# Combined_Board_BMI088.net
KiCad netlist of a schematic drawn in EAGLE
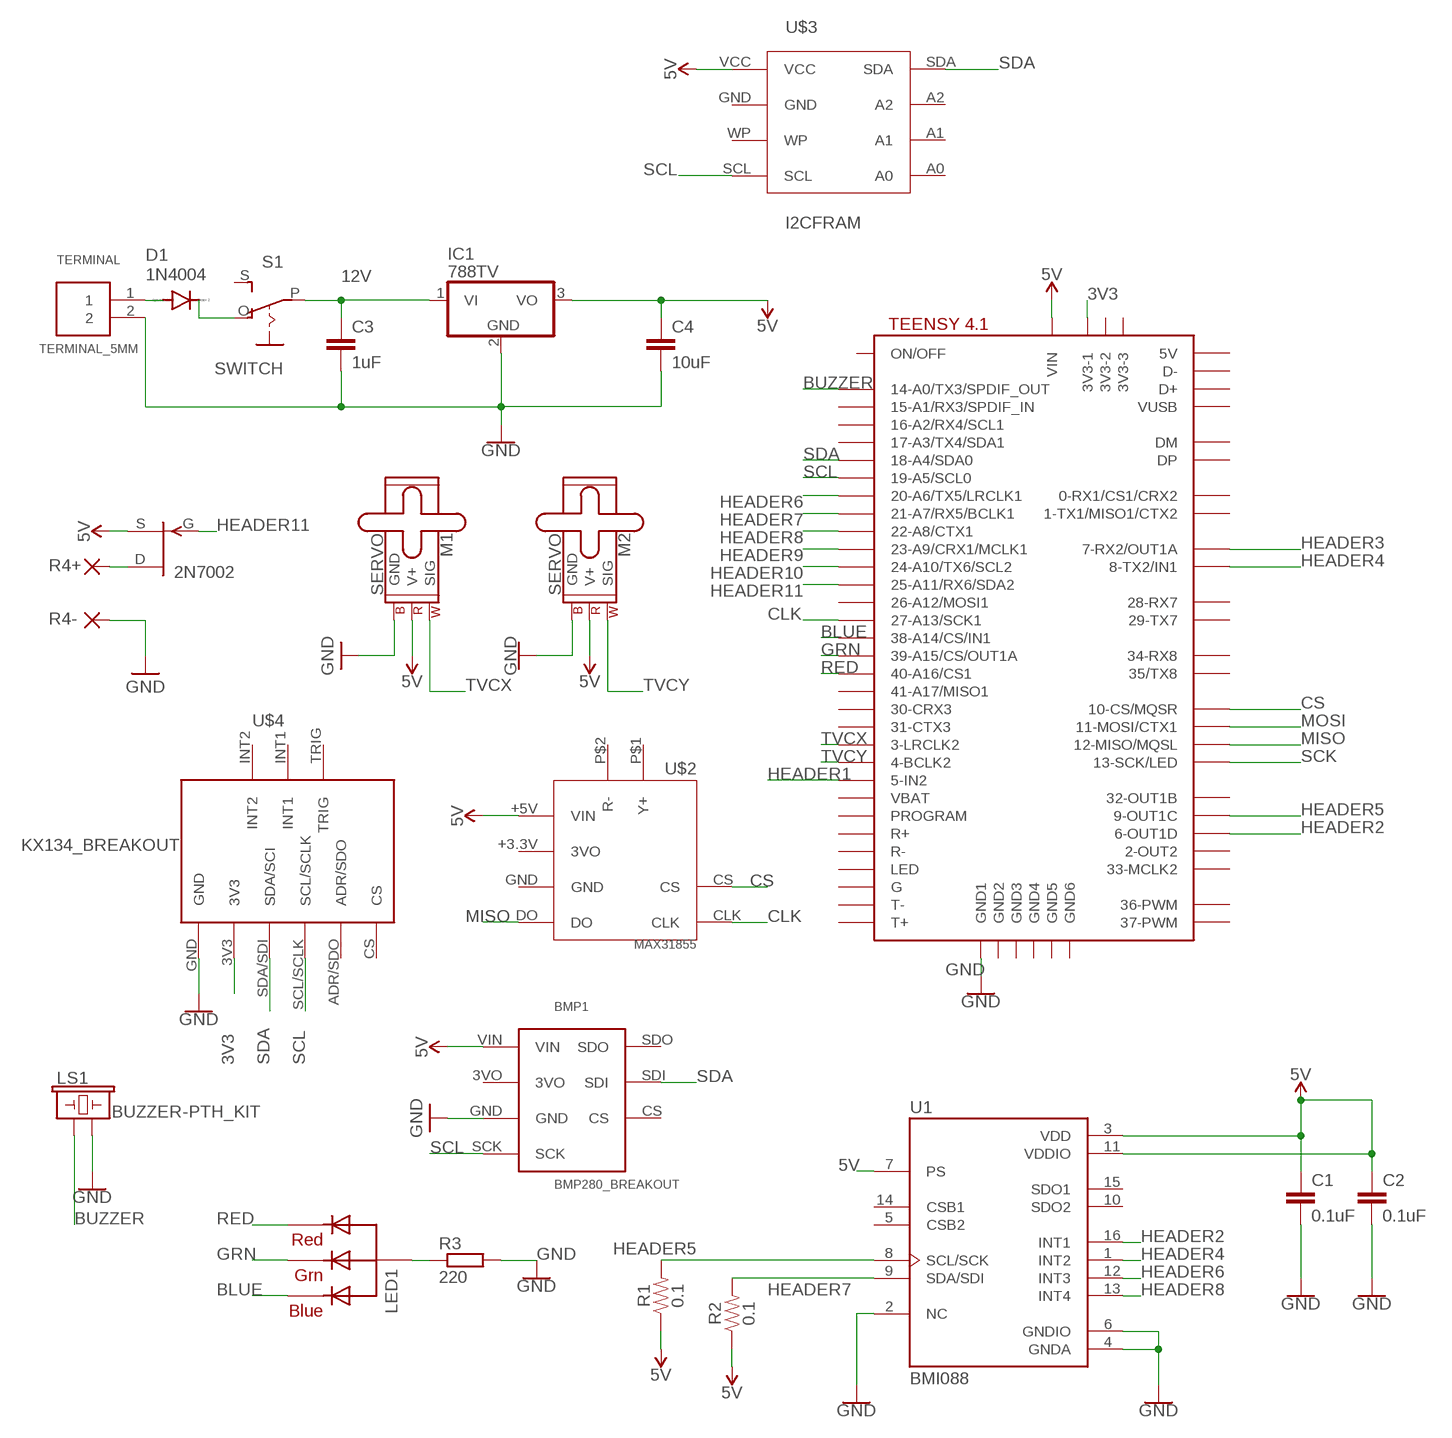
[diagram p0: schematic, sheet 1]

(export (version "E")
  (design (tool "Eeschema 10.0.6"))
  (components
    (comp (ref "2N7002")
      (value "2N3819")
      (footprint "eagle-import:TO92")
      (libsource (lib "eagle-import") (part "2N3819"))
    )
    (comp (ref "BMP1")
      (value "BMP280_BREAKOUT")
      (footprint "eagle-import:BMP280_BREAKOUT")
      (libsource (lib "eagle-import") (part "BMP280_BREAKOUT"))
    )
    (comp (ref "C1")
      (value "0.1uF")
      (footprint "eagle-import:0402")
      (libsource (lib "eagle-import") (part "0.1UF-0402-16V-10%"))
    )
    (comp (ref "C2")
      (value "0.1uF")
      (footprint "eagle-import:0402")
      (libsource (lib "eagle-import") (part "0.1UF-0402-16V-10%"))
    )
    (comp (ref "C3")
      (value "1uF")
      (footprint "eagle-import:CAP-PTH-2.54")
      (libsource (lib "eagle-import") (part "22PF-PTH-2.54MM-200V-5%"))
    )
    (comp (ref "C4")
      (value "10uF")
      (footprint "eagle-import:CAP-PTH-2.54")
      (libsource (lib "eagle-import") (part "22PF-PTH-2.54MM-200V-5%"))
    )
    (comp (ref "D1")
      (value "1N4004")
      (footprint "eagle-import:DO41-10")
      (libsource (lib "eagle-import") (part "1N4004"))
    )
    (comp (ref "IC1")
      (value "788TV")
      (footprint "eagle-import:TO220V")
      (libsource (lib "eagle-import") (part "78TV8"))
    )
    (comp (ref "LED1")
      (value "RGBLED_CA-5MM")
      (footprint "eagle-import:LED5MMRGB")
      (libsource (lib "eagle-import") (part "RGBLED_CA-5MM"))
    )
    (comp (ref "LS1")
      (value "BUZZER-PTH_KIT")
      (footprint "eagle-import:BUZZER-12MM-KIT")
      (libsource (lib "eagle-import") (part "BUZZER-PTH_KIT"))
    )
    (comp (ref "M1")
      (value "SERVO")
      (footprint "eagle-import:1X03")
      (libsource (lib "eagle-import") (part "SERVO"))
    )
    (comp (ref "M2")
      (value "SERVO")
      (footprint "eagle-import:1X03")
      (libsource (lib "eagle-import") (part "SERVO"))
    )
    (comp (ref "R1")
      (value "0.1")
      (footprint "eagle-import:0603")
      (libsource (lib "eagle-import") (part "0.1OHM-0603-1/3W-1%"))
    )
    (comp (ref "R2")
      (value "0.1")
      (footprint "eagle-import:0603")
      (libsource (lib "eagle-import") (part "0.1OHM-0603-1/3W-1%"))
    )
    (comp (ref "R3")
      (value "220")
      (footprint "eagle-import:0204_7")
      (libsource (lib "eagle-import") (part "R-EU_0204/7"))
    )
    (comp (ref "R4+")
      (value "1,6/0,8")
      (footprint "eagle-import:1,6_0,8")
      (libsource (lib "eagle-import") (part "1,6/0,8"))
    )
    (comp (ref "R4-")
      (value "1,6/0,8")
      (footprint "eagle-import:1,6_0,8")
      (libsource (lib "eagle-import") (part "1,6/0,8"))
    )
    (comp (ref "S1")
      (value "SWITCH")
      (footprint "eagle-import:EG1218")
      (libsource (lib "eagle-import") (part "EG1218S"))
    )
    (comp (ref "TERMINAL")
      (value "TERMINAL_5MM")
      (footprint "eagle-import:TERMINAL_5MM")
      (libsource (lib "eagle-import") (part "TERMINAL_5MM"))
    )
    (comp (ref "U$1")
      (value "TEENSY41")
      (footprint "eagle-import:TEENSY41")
      (libsource (lib "eagle-import") (part "TEENSY41"))
    )
    (comp (ref "U$2")
      (value "MAX31855")
      (footprint "eagle-import:MAX31855-BREAKOUT")
      (libsource (lib "eagle-import") (part "MAX31855"))
    )
    (comp (ref "U$3")
      (value "I2CFRAM")
      (footprint "eagle-import:I2CFRAM")
      (libsource (lib "eagle-import") (part "I2CFRAM"))
    )
    (comp (ref "U$4")
      (value "KX134_BREAKOUT")
      (footprint "eagle-import:KX134_BREAKOUT")
      (libsource (lib "eagle-import") (part "KX134_BREAKOUT"))
    )
    (comp (ref "U1")
      (value "BMI088")
      (footprint "eagle-import:PQFN50P450X300X100-16N")
      (fields (field (name "MF") "Bosch Sensortec"))
      (libsource (lib "eagle-import") (part "BMI088"))
    )
  )
  (nets
    (net (code "1") (name "/3V3") (class "Default")
      (node (ref "U$1") (pin "3V3-1") (pinfunction "3V3-1_3V3-1") (pintype "bidirectional"))
      (node (ref "U$4") (pin "3V3") (pinfunction "3V3_3V3") (pintype "bidirectional"))
    )
    (net (code "2") (name "/12V") (class "Default")
      (node (ref "C3") (pin "1") (pinfunction "1_1") (pintype "passive"))
      (node (ref "IC1") (pin "1") (pinfunction "VI_1") (pintype "input"))
      (node (ref "S1") (pin "P") (pinfunction "P_P") (pintype "passive"))
    )
    (net (code "3") (name "/BLUE") (class "Default")
      (node (ref "LED1") (pin "4") (pinfunction "BLUE_4") (pintype "bidirectional"))
      (node (ref "U$1") (pin "38-A14/CS/IN1") (pinfunction "38-A14/CS/IN1_38-A14/CS/IN1") (pintype "bidirectional"))
    )
    (net (code "4") (name "/BUZZER") (class "Default")
      (node (ref "LS1") (pin "+") (pinfunction "1_+") (pintype "passive"))
      (node (ref "U$1") (pin "14-A0/TX3/SPDIF_OUT") (pinfunction "14-A0/TX3/SPDIF_OUT_14-A0/TX3/SPDIF_OUT") (pintype "bidirectional"))
    )
    (net (code "5") (name "/CLK") (class "Default")
      (node (ref "U$1") (pin "27-A13/SCK1") (pinfunction "27-A13/SCK1_27-A13/SCK1") (pintype "bidirectional"))
      (node (ref "U$2") (pin "CLK") (pinfunction "CLK_CLK") (pintype "input"))
    )
    (net (code "6") (name "/CS") (class "Default")
      (node (ref "U$1") (pin "10-CS\\MQSR") (pinfunction "10-CS/MQSR_10-CS\\MQSR") (pintype "bidirectional"))
      (node (ref "U$2") (pin "CS") (pinfunction "CS_CS") (pintype "input"))
    )
    (net (code "7") (name "/GRN") (class "Default")
      (node (ref "LED1") (pin "3") (pinfunction "GREEN_3") (pintype "bidirectional"))
      (node (ref "U$1") (pin "39-A15/CS/OUT1A") (pinfunction "39-A15/CS/OUT1A_39-A15/CS/OUT1A") (pintype "bidirectional"))
    )
    (net (code "8") (name "/HEADER1") (class "Default")
      (node (ref "U$1") (pin "5-IN2") (pinfunction "5-IN2_5-IN2") (pintype "bidirectional"))
    )
    (net (code "9") (name "/HEADER2") (class "Default")
      (node (ref "U$1") (pin "6-OUT1D") (pinfunction "6-OUT1D_6-OUT1D") (pintype "bidirectional"))
      (node (ref "U1") (pin "16") (pinfunction "INT1_16") (pintype "bidirectional"))
    )
    (net (code "10") (name "/HEADER3") (class "Default")
      (node (ref "U$1") (pin "7-RX2/OUT1A") (pinfunction "7-RX2/OUT1A_7-RX2/OUT1A") (pintype "bidirectional"))
    )
    (net (code "11") (name "/HEADER4") (class "Default")
      (node (ref "U$1") (pin "8-TX2/IN2") (pinfunction "8-TX2/IN1_8-TX2/IN2") (pintype "bidirectional"))
      (node (ref "U1") (pin "1") (pinfunction "INT2_1") (pintype "bidirectional"))
    )
    (net (code "12") (name "/HEADER5") (class "Default")
      (node (ref "R1") (pin "2") (pinfunction "2_2") (pintype "passive"))
      (node (ref "U$1") (pin "9-OUT1C") (pinfunction "9-OUT1C_9-OUT1C") (pintype "bidirectional"))
      (node (ref "U1") (pin "8") (pinfunction "SCL/SCK_8") (pintype "input"))
    )
    (net (code "13") (name "/HEADER6") (class "Default")
      (node (ref "U$1") (pin "20-A6/TX5/LRCLK1") (pinfunction "20-A6/TX5/LRCLK1_20-A6/TX5/LRCLK1") (pintype "bidirectional"))
      (node (ref "U1") (pin "12") (pinfunction "INT3_12") (pintype "bidirectional"))
    )
    (net (code "14") (name "/HEADER7") (class "Default")
      (node (ref "R2") (pin "2") (pinfunction "2_2") (pintype "passive"))
      (node (ref "U$1") (pin "21-A7/RX5/BCLK1") (pinfunction "21-A7/RX5/BCLK1_21-A7/RX5/BCLK1") (pintype "bidirectional"))
      (node (ref "U1") (pin "9") (pinfunction "SDA/SDI_9") (pintype "bidirectional"))
    )
    (net (code "15") (name "/HEADER8") (class "Default")
      (node (ref "U$1") (pin "22-A8/CTX1") (pinfunction "22-A8/CTX1_22-A8/CTX1") (pintype "bidirectional"))
      (node (ref "U1") (pin "13") (pinfunction "INT4_13") (pintype "bidirectional"))
    )
    (net (code "16") (name "/HEADER9") (class "Default")
      (node (ref "U$1") (pin "23-A9/CRX1/MCLK1") (pinfunction "23-A9/CRX1/MCLK1_23-A9/CRX1/MCLK1") (pintype "bidirectional"))
    )
    (net (code "17") (name "/HEADER10") (class "Default")
      (node (ref "U$1") (pin "24-A10/TX6/SCL2") (pinfunction "24-A10/TX6/SCL2_24-A10/TX6/SCL2") (pintype "bidirectional"))
    )
    (net (code "18") (name "/HEADER11") (class "Default")
      (node (ref "2N7002") (pin "2") (pinfunction "G_2") (pintype "passive"))
      (node (ref "U$1") (pin "25-A11/RX6/SDA2") (pinfunction "25-A11/RX6/SDA2_25-A11/RX6/SDA2") (pintype "bidirectional"))
    )
    (net (code "19") (name "/MISO") (class "Default")
      (node (ref "U$1") (pin "12-MISO/MQSL") (pinfunction "12-MISO/MQSL_12-MISO/MQSL") (pintype "bidirectional"))
      (node (ref "U$2") (pin "DO") (pinfunction "DO_DO") (pintype "output"))
    )
    (net (code "20") (name "/MOSI") (class "Default")
      (node (ref "U$1") (pin "11-MOSI/CTX1") (pinfunction "11-MOSI/CTX1_11-MOSI/CTX1") (pintype "bidirectional"))
    )
    (net (code "21") (name "/RED") (class "Default")
      (node (ref "LED1") (pin "1") (pinfunction "RED_1") (pintype "bidirectional"))
      (node (ref "U$1") (pin "40-A16/CS1") (pinfunction "40-A16/CS1_40-A16/CS1") (pintype "bidirectional"))
    )
    (net (code "22") (name "/SCK") (class "Default")
      (node (ref "U$1") (pin "13-SCK/LED") (pinfunction "13-SCK/LED_13-SCK/LED") (pintype "bidirectional"))
    )
    (net (code "23") (name "/SCL") (class "Default")
      (node (ref "BMP1") (pin "SCK") (pinfunction "SCK_SCK") (pintype "bidirectional"))
      (node (ref "U$1") (pin "19-A5/SCL0") (pinfunction "19-A5/SCL0_19-A5/SCL0") (pintype "bidirectional"))
      (node (ref "U$3") (pin "SCL") (pinfunction "SCL_SCL") (pintype "bidirectional"))
      (node (ref "U$4") (pin "SCL/SCLK") (pinfunction "SCL/SCLK_SCL/SCLK") (pintype "bidirectional"))
    )
    (net (code "24") (name "/SDA") (class "Default")
      (node (ref "BMP1") (pin "SDI") (pinfunction "SDI_SDI") (pintype "bidirectional"))
      (node (ref "U$1") (pin "18-A4/SDA0") (pinfunction "18-A4/SDA0_18-A4/SDA0") (pintype "bidirectional"))
      (node (ref "U$3") (pin "SDA") (pinfunction "SDA_SDA") (pintype "bidirectional"))
      (node (ref "U$4") (pin "SDA/SDI") (pinfunction "SDA/SCI_SDA/SDI") (pintype "bidirectional"))
    )
    (net (code "25") (name "/TVCX") (class "Default")
      (node (ref "M1") (pin "1") (pinfunction "SIG_1") (pintype "bidirectional"))
      (node (ref "U$1") (pin "3-LRCLK2") (pinfunction "3-LRCLK2_3-LRCLK2") (pintype "bidirectional"))
    )
    (net (code "26") (name "/TVCY") (class "Default")
      (node (ref "M2") (pin "1") (pinfunction "SIG_1") (pintype "bidirectional"))
      (node (ref "U$1") (pin "4-BCLK2") (pinfunction "4-BCLK2_4-BCLK2") (pintype "bidirectional"))
    )
    (net (code "27") (name "5V") (class "Default")
      (node (ref "2N7002") (pin "3") (pinfunction "S_3") (pintype "passive"))
      (node (ref "BMP1") (pin "VIN") (pinfunction "VIN_VIN") (pintype "bidirectional"))
      (node (ref "C1") (pin "1") (pinfunction "1_1") (pintype "passive"))
      (node (ref "C2") (pin "1") (pinfunction "1_1") (pintype "passive"))
      (node (ref "C4") (pin "1") (pinfunction "1_1") (pintype "passive"))
      (node (ref "IC1") (pin "3") (pinfunction "VO_3") (pintype "passive"))
      (node (ref "M1") (pin "2") (pinfunction "V+_2") (pintype "bidirectional"))
      (node (ref "M2") (pin "2") (pinfunction "V+_2") (pintype "bidirectional"))
      (node (ref "R1") (pin "1") (pinfunction "1_1") (pintype "passive"))
      (node (ref "R2") (pin "1") (pinfunction "1_1") (pintype "passive"))
      (node (ref "U$1") (pin "VIN") (pinfunction "VIN_VIN") (pintype "bidirectional"))
      (node (ref "U$2") (pin "+5V") (pinfunction "VIN_+5V") (pintype "input"))
      (node (ref "U$3") (pin "VCC") (pinfunction "VCC_VCC") (pintype "bidirectional"))
      (node (ref "U1") (pin "11") (pinfunction "VDDIO_11") (pintype "power_in"))
      (node (ref "U1") (pin "3") (pinfunction "VDD_3") (pintype "power_in"))
      (node (ref "U1") (pin "7") (pinfunction "PS_7") (pintype "input"))
    )
    (net (code "28") (name "GND") (class "Default")
      (node (ref "BMP1") (pin "GND") (pinfunction "GND_GND") (pintype "bidirectional"))
      (node (ref "C1") (pin "2") (pinfunction "2_2") (pintype "passive"))
      (node (ref "C2") (pin "2") (pinfunction "2_2") (pintype "passive"))
      (node (ref "C3") (pin "2") (pinfunction "2_2") (pintype "passive"))
      (node (ref "C4") (pin "2") (pinfunction "2_2") (pintype "passive"))
      (node (ref "IC1") (pin "2") (pinfunction "GND_2") (pintype "passive"))
      (node (ref "LS1") (pin "-") (pinfunction "2_-") (pintype "passive"))
      (node (ref "M1") (pin "3") (pinfunction "GND_3") (pintype "bidirectional"))
      (node (ref "M2") (pin "3") (pinfunction "GND_3") (pintype "bidirectional"))
      (node (ref "R3") (pin "2") (pinfunction "2_2") (pintype "passive"))
      (node (ref "R4-") (pin "1") (pinfunction "P_1") (pintype "passive"))
      (node (ref "TERMINAL") (pin "2") (pinfunction "2_2") (pintype "bidirectional"))
      (node (ref "U$1") (pin "GND1") (pinfunction "GND1_GND1") (pintype "bidirectional"))
      (node (ref "U$4") (pin "GND") (pinfunction "GND_GND") (pintype "bidirectional"))
      (node (ref "U1") (pin "2") (pinfunction "NC_2") (pintype "passive"))
      (node (ref "U1") (pin "4") (pinfunction "GNDA_4") (pintype "power_in"))
      (node (ref "U1") (pin "6") (pinfunction "GNDIO_6") (pintype "power_in"))
    )
    (net (code "29") (name "Net-(2N7002-D)") (class "Default")
      (node (ref "2N7002") (pin "1") (pinfunction "D_1") (pintype "passive"))
      (node (ref "R4+") (pin "1") (pinfunction "P_1") (pintype "passive"))
    )
    (net (code "30") (name "Net-(D1-PadA)") (class "Default")
      (node (ref "D1") (pin "A") (pinfunction "A_A") (pintype "passive"))
      (node (ref "TERMINAL") (pin "1") (pinfunction "1_1") (pintype "bidirectional"))
    )
    (net (code "31") (name "Net-(D1-PadC)") (class "Default")
      (node (ref "D1") (pin "C") (pinfunction "C_C") (pintype "passive"))
      (node (ref "S1") (pin "O") (pinfunction "O_O") (pintype "passive"))
    )
    (net (code "32") (name "Net-(LED1-VCC)") (class "Default")
      (node (ref "LED1") (pin "2") (pinfunction "VCC_2") (pintype "bidirectional"))
      (node (ref "R3") (pin "1") (pinfunction "1_1") (pintype "passive"))
    )
    (net (code "33") (name "unconnected-(BMP1-Pad3VO)") (class "Default")
      (node (ref "BMP1") (pin "3VO") (pinfunction "3VO_3VO") (pintype "bidirectional"))
    )
    (net (code "34") (name "unconnected-(BMP1-PadCS)") (class "Default")
      (node (ref "BMP1") (pin "CS") (pinfunction "CS_CS") (pintype "bidirectional"))
    )
    (net (code "35") (name "unconnected-(BMP1-PadSDO)") (class "Default")
      (node (ref "BMP1") (pin "SDO") (pinfunction "SDO_SDO") (pintype "bidirectional"))
    )
    (net (code "36") (name "unconnected-(S1-PadS)") (class "Default")
      (node (ref "S1") (pin "S") (pinfunction "S_S") (pintype "passive"))
    )
    (net (code "37") (name "unconnected-(U$1-5V-Pad+5V)") (class "Default")
      (node (ref "U$1") (pin "+5V") (pinfunction "5V_+5V") (pintype "bidirectional"))
    )
    (net (code "38") (name "unconnected-(U$1-35{slash}TX8-Pad35-TX8)") (class "Default")
      (node (ref "U$1") (pin "35-TX8") (pinfunction "35/TX8_35-TX8") (pintype "bidirectional"))
    )
    (net (code "39") (name "unconnected-(U$1-Pad0-RX1{slash}CS1{slash}CRX2)") (class "Default")
      (node (ref "U$1") (pin "0-RX1/CS1/CRX2") (pinfunction "0-RX1/CS1/CRX2_0-RX1/CS1/CRX2") (pintype "bidirectional"))
    )
    (net (code "40") (name "unconnected-(U$1-Pad1-TX1{slash}MISO1{slash}CTX2)") (class "Default")
      (node (ref "U$1") (pin "1-TX1/MISO1/CTX2") (pinfunction "1-TX1/MISO1/CTX2_1-TX1/MISO1/CTX2") (pintype "bidirectional"))
    )
    (net (code "41") (name "unconnected-(U$1-Pad2-OUT2)") (class "Default")
      (node (ref "U$1") (pin "2-OUT2") (pinfunction "2-OUT2_2-OUT2") (pintype "bidirectional"))
    )
    (net (code "42") (name "unconnected-(U$1-Pad3V3-2)") (class "Default")
      (node (ref "U$1") (pin "3V3-2") (pinfunction "3V3-2_3V3-2") (pintype "bidirectional"))
    )
    (net (code "43") (name "unconnected-(U$1-Pad3V3-3)") (class "Default")
      (node (ref "U$1") (pin "3V3-3") (pinfunction "3V3-3_3V3-3") (pintype "bidirectional"))
    )
    (net (code "44") (name "unconnected-(U$1-Pad15-A1{slash}RX3{slash}SPDIF_IN)") (class "Default")
      (node (ref "U$1") (pin "15-A1/RX3/SPDIF_IN") (pinfunction "15-A1/RX3/SPDIF_IN_15-A1/RX3/SPDIF_IN") (pintype "bidirectional"))
    )
    (net (code "45") (name "unconnected-(U$1-Pad16-A2{slash}RX4{slash}SCL1)") (class "Default")
      (node (ref "U$1") (pin "16-A2/RX4/SCL1") (pinfunction "16-A2/RX4/SCL1_16-A2/RX4/SCL1") (pintype "bidirectional"))
    )
    (net (code "46") (name "unconnected-(U$1-Pad17-A3{slash}TX4{slash}SDA1)") (class "Default")
      (node (ref "U$1") (pin "17-A3/TX4/SDA1") (pinfunction "17-A3/TX4/SDA1_17-A3/TX4/SDA1") (pintype "bidirectional"))
    )
    (net (code "47") (name "unconnected-(U$1-Pad26-A12{slash}MOSI1)") (class "Default")
      (node (ref "U$1") (pin "26-A12/MOSI1") (pinfunction "26-A12/MOSI1_26-A12/MOSI1") (pintype "bidirectional"))
    )
    (net (code "48") (name "unconnected-(U$1-Pad28-RX7)") (class "Default")
      (node (ref "U$1") (pin "28-RX7") (pinfunction "28-RX7_28-RX7") (pintype "bidirectional"))
    )
    (net (code "49") (name "unconnected-(U$1-Pad29-TX7)") (class "Default")
      (node (ref "U$1") (pin "29-TX7") (pinfunction "29-TX7_29-TX7") (pintype "bidirectional"))
    )
    (net (code "50") (name "unconnected-(U$1-Pad30-CRX3)") (class "Default")
      (node (ref "U$1") (pin "30-CRX3") (pinfunction "30-CRX3_30-CRX3") (pintype "bidirectional"))
    )
    (net (code "51") (name "unconnected-(U$1-Pad31-CTX3)") (class "Default")
      (node (ref "U$1") (pin "31-CTX3") (pinfunction "31-CTX3_31-CTX3") (pintype "bidirectional"))
    )
    (net (code "52") (name "unconnected-(U$1-Pad32-OUT1B)") (class "Default")
      (node (ref "U$1") (pin "32-OUT1B") (pinfunction "32-OUT1B_32-OUT1B") (pintype "bidirectional"))
    )
    (net (code "53") (name "unconnected-(U$1-Pad33-MCLK2)") (class "Default")
      (node (ref "U$1") (pin "33-MCLK2") (pinfunction "33-MCLK2_33-MCLK2") (pintype "bidirectional"))
    )
    (net (code "54") (name "unconnected-(U$1-Pad34-RX8)") (class "Default")
      (node (ref "U$1") (pin "34-RX8") (pinfunction "34-RX8_34-RX8") (pintype "bidirectional"))
    )
    (net (code "55") (name "unconnected-(U$1-Pad36-PWM)") (class "Default")
      (node (ref "U$1") (pin "36-PWM") (pinfunction "36-PWM_36-PWM") (pintype "bidirectional"))
    )
    (net (code "56") (name "unconnected-(U$1-Pad37-PWM)") (class "Default")
      (node (ref "U$1") (pin "37-PWM") (pinfunction "37-PWM_37-PWM") (pintype "bidirectional"))
    )
    (net (code "57") (name "unconnected-(U$1-Pad41-A17{slash}MISO1)") (class "Default")
      (node (ref "U$1") (pin "41-A17/MISO1") (pinfunction "41-A17/MISO1_41-A17/MISO1") (pintype "bidirectional"))
    )
    (net (code "58") (name "unconnected-(U$1-PadD+)") (class "Default")
      (node (ref "U$1") (pin "D+") (pinfunction "D+_D+") (pintype "bidirectional"))
    )
    (net (code "59") (name "unconnected-(U$1-PadD-)") (class "Default")
      (node (ref "U$1") (pin "D-") (pinfunction "D-_D-") (pintype "bidirectional"))
    )
    (net (code "60") (name "unconnected-(U$1-PadDM)") (class "Default")
      (node (ref "U$1") (pin "DM") (pinfunction "DM_DM") (pintype "bidirectional"))
    )
    (net (code "61") (name "unconnected-(U$1-PadDP)") (class "Default")
      (node (ref "U$1") (pin "DP") (pinfunction "DP_DP") (pintype "bidirectional"))
    )
    (net (code "62") (name "unconnected-(U$1-PadG)") (class "Default")
      (node (ref "U$1") (pin "G") (pinfunction "G_G") (pintype "bidirectional"))
    )
    (net (code "63") (name "unconnected-(U$1-PadGND2)") (class "Default")
      (node (ref "U$1") (pin "GND2") (pinfunction "GND2_GND2") (pintype "bidirectional"))
    )
    (net (code "64") (name "unconnected-(U$1-PadGND3)") (class "Default")
      (node (ref "U$1") (pin "GND3") (pinfunction "GND3_GND3") (pintype "bidirectional"))
    )
    (net (code "65") (name "unconnected-(U$1-PadGND4)") (class "Default")
      (node (ref "U$1") (pin "GND4") (pinfunction "GND4_GND4") (pintype "bidirectional"))
    )
    (net (code "66") (name "unconnected-(U$1-PadGND5)") (class "Default")
      (node (ref "U$1") (pin "GND5") (pinfunction "GND5_GND5") (pintype "bidirectional"))
    )
    (net (code "67") (name "unconnected-(U$1-PadGND6)") (class "Default")
      (node (ref "U$1") (pin "GND6") (pinfunction "GND6_GND6") (pintype "bidirectional"))
    )
    (net (code "68") (name "unconnected-(U$1-PadLED)") (class "Default")
      (node (ref "U$1") (pin "LED") (pinfunction "LED_LED") (pintype "bidirectional"))
    )
    (net (code "69") (name "unconnected-(U$1-PadON{slash}OFF)") (class "Default")
      (node (ref "U$1") (pin "ON/OFF") (pinfunction "ON/OFF_ON/OFF") (pintype "bidirectional"))
    )
    (net (code "70") (name "unconnected-(U$1-PadPROGRAM)") (class "Default")
      (node (ref "U$1") (pin "PROGRAM") (pinfunction "PROGRAM_PROGRAM") (pintype "bidirectional"))
    )
    (net (code "71") (name "unconnected-(U$1-PadR+)") (class "Default")
      (node (ref "U$1") (pin "R+") (pinfunction "R+_R+") (pintype "bidirectional"))
    )
    (net (code "72") (name "unconnected-(U$1-PadR-)") (class "Default")
      (node (ref "U$1") (pin "R-") (pinfunction "R-_R-") (pintype "bidirectional"))
    )
    (net (code "73") (name "unconnected-(U$1-PadT+)") (class "Default")
      (node (ref "U$1") (pin "T+") (pinfunction "T+_T+") (pintype "bidirectional"))
    )
    (net (code "74") (name "unconnected-(U$1-PadT-)") (class "Default")
      (node (ref "U$1") (pin "T-") (pinfunction "T-_T-") (pintype "bidirectional"))
    )
    (net (code "75") (name "unconnected-(U$1-PadVBAT)") (class "Default")
      (node (ref "U$1") (pin "VBAT") (pinfunction "VBAT_VBAT") (pintype "bidirectional"))
    )
    (net (code "76") (name "unconnected-(U$1-PadVUSB)") (class "Default")
      (node (ref "U$1") (pin "VUSB") (pinfunction "VUSB_VUSB") (pintype "bidirectional"))
    )
    (net (code "77") (name "unconnected-(U$2-3VO-Pad+3.3V)") (class "Default")
      (node (ref "U$2") (pin "+3.3V") (pinfunction "3VO_+3.3V") (pintype "output"))
    )
    (net (code "78") (name "unconnected-(U$2-PadGND)") (class "Default")
      (node (ref "U$2") (pin "GND") (pinfunction "GND_GND") (pintype "input"))
    )
    (net (code "79") (name "unconnected-(U$2-R--PadP$2)") (class "Default")
      (node (ref "U$2") (pin "P$2") (pinfunction "R-_P$2") (pintype "bidirectional"))
    )
    (net (code "80") (name "unconnected-(U$2-Y+-PadP$1)") (class "Default")
      (node (ref "U$2") (pin "P$1") (pinfunction "Y+_P$1") (pintype "bidirectional"))
    )
    (net (code "81") (name "unconnected-(U$3-PadA0)") (class "Default")
      (node (ref "U$3") (pin "A0") (pinfunction "A0_A0") (pintype "bidirectional"))
    )
    (net (code "82") (name "unconnected-(U$3-PadA1)") (class "Default")
      (node (ref "U$3") (pin "A1") (pinfunction "A1_A1") (pintype "bidirectional"))
    )
    (net (code "83") (name "unconnected-(U$3-PadA2)") (class "Default")
      (node (ref "U$3") (pin "A2") (pinfunction "A2_A2") (pintype "bidirectional"))
    )
    (net (code "84") (name "unconnected-(U$3-PadGND)") (class "Default")
      (node (ref "U$3") (pin "GND") (pinfunction "GND_GND") (pintype "bidirectional"))
    )
    (net (code "85") (name "unconnected-(U$3-PadWP)") (class "Default")
      (node (ref "U$3") (pin "WP") (pinfunction "WP_WP") (pintype "bidirectional"))
    )
    (net (code "86") (name "unconnected-(U$4-PadADR{slash}SDO)") (class "Default")
      (node (ref "U$4") (pin "ADR/SDO") (pinfunction "ADR/SDO_ADR/SDO") (pintype "bidirectional"))
    )
    (net (code "87") (name "unconnected-(U$4-PadCS)") (class "Default")
      (node (ref "U$4") (pin "CS") (pinfunction "CS_CS") (pintype "bidirectional"))
    )
    (net (code "88") (name "unconnected-(U$4-PadINT1)") (class "Default")
      (node (ref "U$4") (pin "INT1") (pinfunction "INT1_INT1") (pintype "bidirectional"))
    )
    (net (code "89") (name "unconnected-(U$4-PadINT2)") (class "Default")
      (node (ref "U$4") (pin "INT2") (pinfunction "INT2_INT2") (pintype "bidirectional"))
    )
    (net (code "90") (name "unconnected-(U$4-PadTRIG)") (class "Default")
      (node (ref "U$4") (pin "TRIG") (pinfunction "TRIG_TRIG") (pintype "bidirectional"))
    )
    (net (code "91") (name "unconnected-(U1-CSB1-Pad14)") (class "Default")
      (node (ref "U1") (pin "14") (pinfunction "CSB1_14") (pintype "input"))
    )
    (net (code "92") (name "unconnected-(U1-CSB2-Pad5)") (class "Default")
      (node (ref "U1") (pin "5") (pinfunction "CSB2_5") (pintype "input"))
    )
    (net (code "93") (name "unconnected-(U1-SDO1-Pad15)") (class "Default")
      (node (ref "U1") (pin "15") (pinfunction "SDO1_15") (pintype "output"))
    )
    (net (code "94") (name "unconnected-(U1-SDO2-Pad10)") (class "Default")
      (node (ref "U1") (pin "10") (pinfunction "SDO2_10") (pintype "output"))
    )
  )
)
